# Teensy41Memory.net
KiCad netlist of a schematic drawn in EAGLE
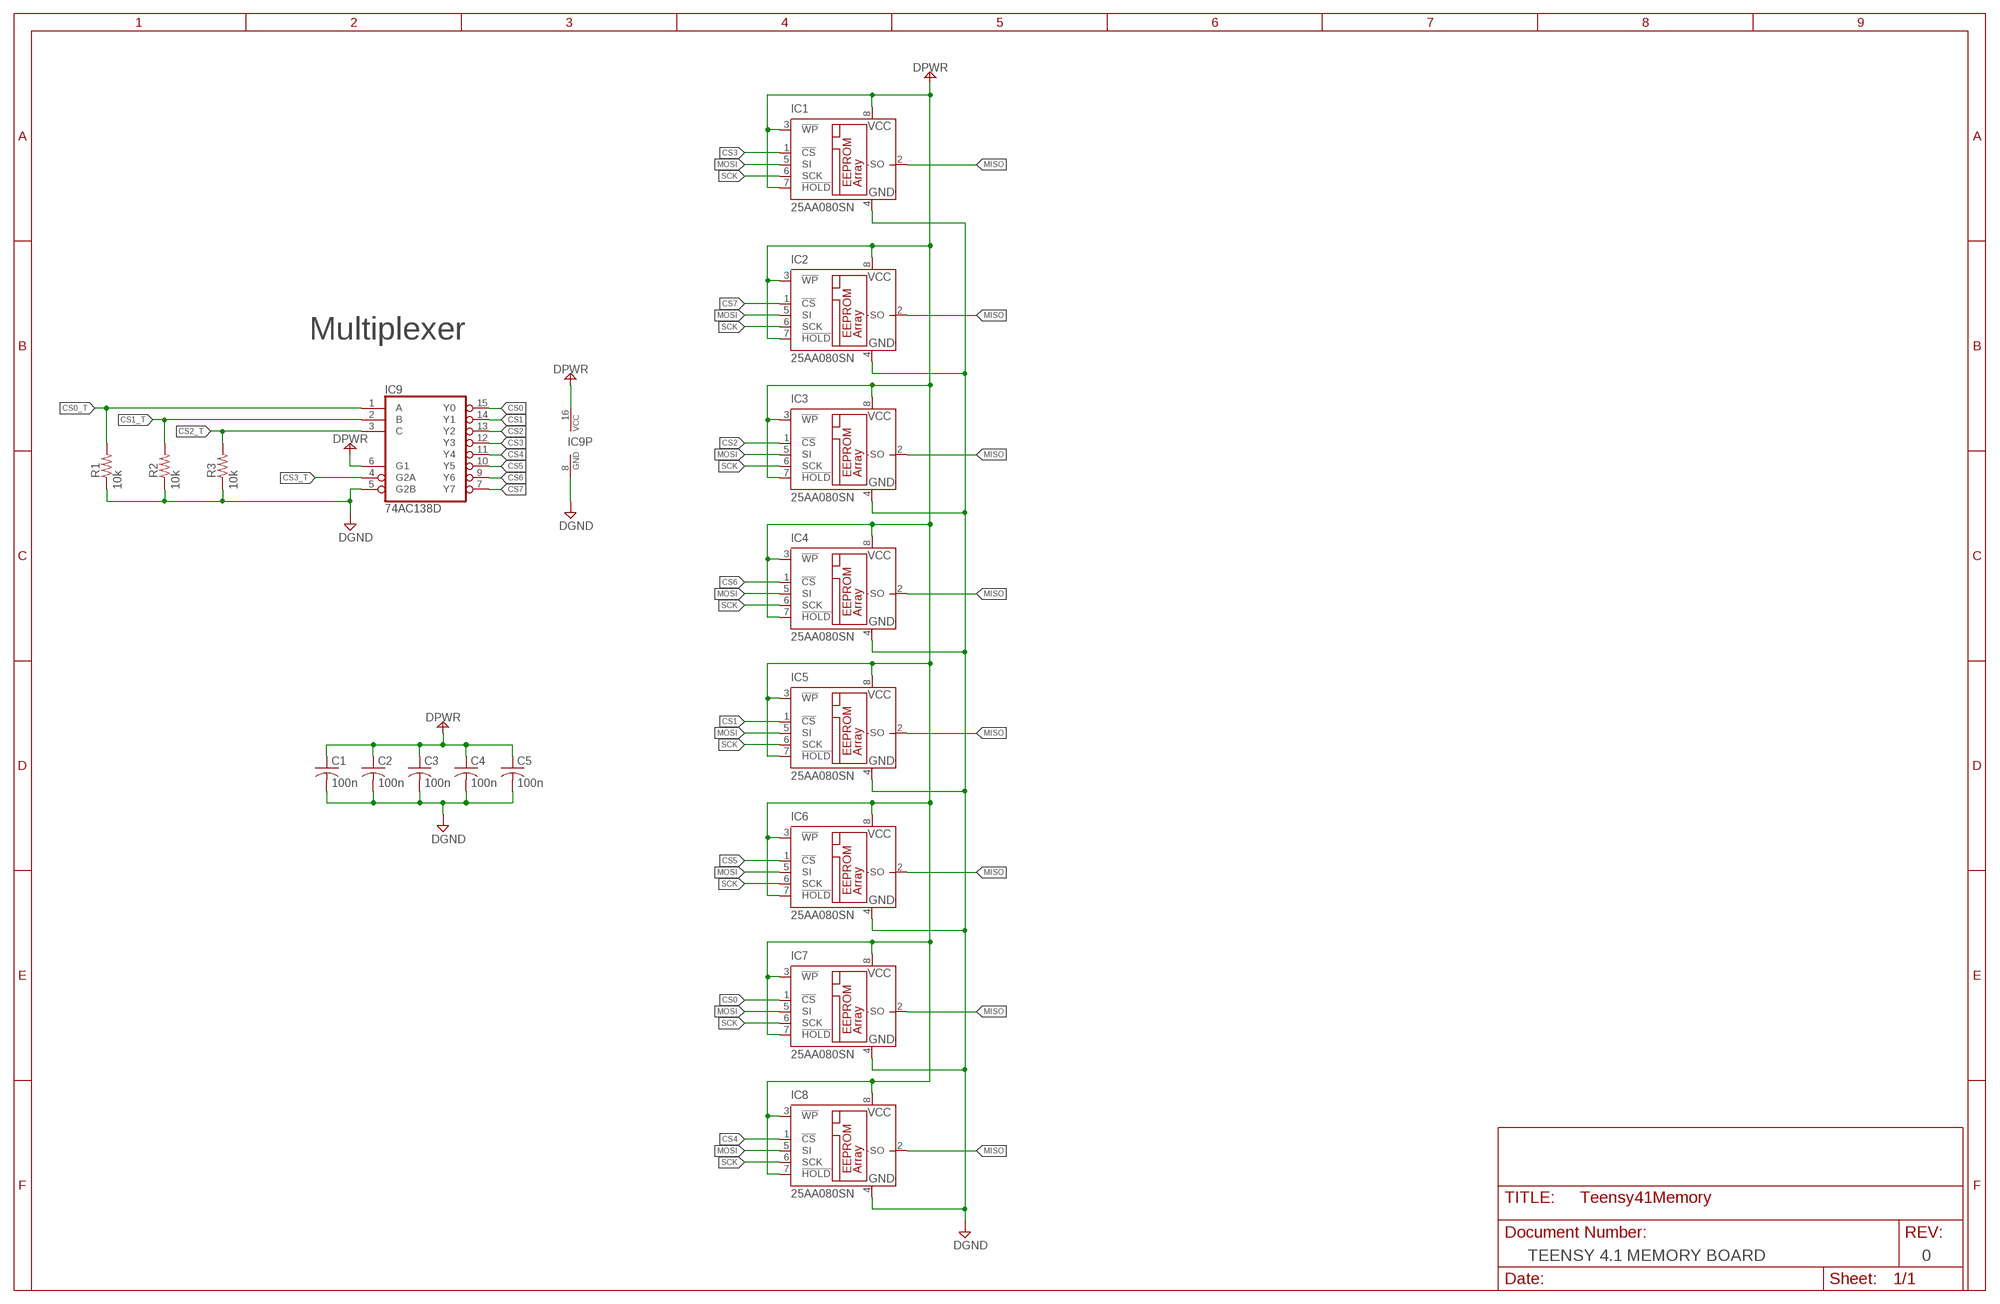
[diagram p0: schematic, sheet 1]

(export (version "E")
  (design (tool "Eeschema 10.0.6"))
  (components
    (comp (ref "C1")
      (value "100n")
      (footprint "eagle-import:C0603")
      (libsource (lib "eagle-import") (part "CB"))
    )
    (comp (ref "C2")
      (value "100n")
      (footprint "eagle-import:C0603")
      (libsource (lib "eagle-import") (part "CB"))
    )
    (comp (ref "C3")
      (value "100n")
      (footprint "eagle-import:C0603")
      (libsource (lib "eagle-import") (part "CB"))
    )
    (comp (ref "C4")
      (value "100n")
      (footprint "eagle-import:C0603")
      (libsource (lib "eagle-import") (part "CB"))
    )
    (comp (ref "C5")
      (value "100n")
      (footprint "eagle-import:C0603")
      (libsource (lib "eagle-import") (part "CB"))
    )
    (comp (ref "IC1")
      (value "25AA080SN")
      (footprint "eagle-import:SO-08")
      (fields (field (name "MF") "MICROCHIP") (field (name "MPN") "25AA080/SN"))
      (libsource (lib "eagle-import") (part "25SNAA080"))
    )
    (comp (ref "IC2")
      (value "25AA080SN")
      (footprint "eagle-import:SO-08")
      (fields (field (name "MF") "MICROCHIP") (field (name "MPN") "25AA080/SN"))
      (libsource (lib "eagle-import") (part "25SNAA080"))
    )
    (comp (ref "IC3")
      (value "25AA080SN")
      (footprint "eagle-import:SO-08")
      (fields (field (name "MF") "MICROCHIP") (field (name "MPN") "25AA080/SN"))
      (libsource (lib "eagle-import") (part "25SNAA080"))
    )
    (comp (ref "IC4")
      (value "25AA080SN")
      (footprint "eagle-import:SO-08")
      (fields (field (name "MF") "MICROCHIP") (field (name "MPN") "25AA080/SN"))
      (libsource (lib "eagle-import") (part "25SNAA080"))
    )
    (comp (ref "IC5")
      (value "25AA080SN")
      (footprint "eagle-import:SO-08")
      (fields (field (name "MF") "MICROCHIP") (field (name "MPN") "25AA080/SN"))
      (libsource (lib "eagle-import") (part "25SNAA080"))
    )
    (comp (ref "IC6")
      (value "25AA080SN")
      (footprint "eagle-import:SO-08")
      (fields (field (name "MF") "MICROCHIP") (field (name "MPN") "25AA080/SN"))
      (libsource (lib "eagle-import") (part "25SNAA080"))
    )
    (comp (ref "IC7")
      (value "25AA080SN")
      (footprint "eagle-import:SO-08")
      (fields (field (name "MF") "MICROCHIP") (field (name "MPN") "25AA080/SN"))
      (libsource (lib "eagle-import") (part "25SNAA080"))
    )
    (comp (ref "IC8")
      (value "25AA080SN")
      (footprint "eagle-import:SO-08")
      (fields (field (name "MF") "MICROCHIP") (field (name "MPN") "25AA080/SN"))
      (libsource (lib "eagle-import") (part "25SNAA080"))
    )
    (comp (ref "IC9")
      (value "74AC138D")
      (footprint "eagle-import:SO16")
      (libsource (lib "eagle-import") (part "74138DAC"))
    )
    (comp (ref "R1")
      (value "10k")
      (footprint "eagle-import:R0603")
      (libsource (lib "eagle-import") (part "RB"))
    )
    (comp (ref "R2")
      (value "10k")
      (footprint "eagle-import:R0603")
      (libsource (lib "eagle-import") (part "RB"))
    )
    (comp (ref "R3")
      (value "10k")
      (footprint "eagle-import:R0603")
      (libsource (lib "eagle-import") (part "RB"))
    )
  )
  (nets
    (net (code "1") (name "CS0") (class "Default")
      (node (ref "IC7") (pin "1") (pinfunction "~{CS}_1") (pintype "input"))
      (node (ref "IC9") (pin "15") (pinfunction "Y0_15") (pintype "output"))
    )
    (net (code "2") (name "CS0_T") (class "Default")
      (node (ref "IC9") (pin "1") (pinfunction "A_1") (pintype "input"))
      (node (ref "R1") (pin "2") (pinfunction "2_2") (pintype "passive"))
    )
    (net (code "3") (name "CS1") (class "Default")
      (node (ref "IC5") (pin "1") (pinfunction "~{CS}_1") (pintype "input"))
      (node (ref "IC9") (pin "14") (pinfunction "Y1_14") (pintype "output"))
    )
    (net (code "4") (name "CS1_T") (class "Default")
      (node (ref "IC9") (pin "2") (pinfunction "B_2") (pintype "input"))
      (node (ref "R2") (pin "2") (pinfunction "2_2") (pintype "passive"))
    )
    (net (code "5") (name "CS2") (class "Default")
      (node (ref "IC3") (pin "1") (pinfunction "~{CS}_1") (pintype "input"))
      (node (ref "IC9") (pin "13") (pinfunction "Y2_13") (pintype "output"))
    )
    (net (code "6") (name "CS2_T") (class "Default")
      (node (ref "IC9") (pin "3") (pinfunction "C_3") (pintype "input"))
      (node (ref "R3") (pin "2") (pinfunction "2_2") (pintype "passive"))
    )
    (net (code "7") (name "CS3") (class "Default")
      (node (ref "IC1") (pin "1") (pinfunction "~{CS}_1") (pintype "input"))
      (node (ref "IC9") (pin "12") (pinfunction "Y3_12") (pintype "output"))
    )
    (net (code "8") (name "CS3_T") (class "Default")
      (node (ref "IC9") (pin "4") (pinfunction "G2A_4") (pintype "input"))
    )
    (net (code "9") (name "CS4") (class "Default")
      (node (ref "IC8") (pin "1") (pinfunction "~{CS}_1") (pintype "input"))
      (node (ref "IC9") (pin "11") (pinfunction "Y4_11") (pintype "output"))
    )
    (net (code "10") (name "CS5") (class "Default")
      (node (ref "IC6") (pin "1") (pinfunction "~{CS}_1") (pintype "input"))
      (node (ref "IC9") (pin "10") (pinfunction "Y5_10") (pintype "output"))
    )
    (net (code "11") (name "CS6") (class "Default")
      (node (ref "IC4") (pin "1") (pinfunction "~{CS}_1") (pintype "input"))
      (node (ref "IC9") (pin "9") (pinfunction "Y6_9") (pintype "output"))
    )
    (net (code "12") (name "CS7") (class "Default")
      (node (ref "IC2") (pin "1") (pinfunction "~{CS}_1") (pintype "input"))
      (node (ref "IC9") (pin "7") (pinfunction "Y7_7") (pintype "output"))
    )
    (net (code "13") (name "DGND") (class "Default")
      (node (ref "C1") (pin "2") (pinfunction "2_2") (pintype "passive"))
      (node (ref "C2") (pin "2") (pinfunction "2_2") (pintype "passive"))
      (node (ref "C3") (pin "2") (pinfunction "2_2") (pintype "passive"))
      (node (ref "C4") (pin "2") (pinfunction "2_2") (pintype "passive"))
      (node (ref "C5") (pin "2") (pinfunction "2_2") (pintype "passive"))
      (node (ref "IC1") (pin "4") (pinfunction "GND_4") (pintype "power_in"))
      (node (ref "IC2") (pin "4") (pinfunction "GND_4") (pintype "power_in"))
      (node (ref "IC3") (pin "4") (pinfunction "GND_4") (pintype "power_in"))
      (node (ref "IC4") (pin "4") (pinfunction "GND_4") (pintype "power_in"))
      (node (ref "IC5") (pin "4") (pinfunction "GND_4") (pintype "power_in"))
      (node (ref "IC6") (pin "4") (pinfunction "GND_4") (pintype "power_in"))
      (node (ref "IC7") (pin "4") (pinfunction "GND_4") (pintype "power_in"))
      (node (ref "IC8") (pin "4") (pinfunction "GND_4") (pintype "power_in"))
      (node (ref "IC9") (pin "5") (pinfunction "G2B_5") (pintype "input"))
      (node (ref "IC9") (pin "8") (pinfunction "GND_8") (pintype "power_in"))
      (node (ref "R1") (pin "1") (pinfunction "1_1") (pintype "passive"))
      (node (ref "R2") (pin "1") (pinfunction "1_1") (pintype "passive"))
      (node (ref "R3") (pin "1") (pinfunction "1_1") (pintype "passive"))
    )
    (net (code "14") (name "DPWR") (class "Default")
      (node (ref "C1") (pin "1") (pinfunction "1_1") (pintype "passive"))
      (node (ref "C2") (pin "1") (pinfunction "1_1") (pintype "passive"))
      (node (ref "C3") (pin "1") (pinfunction "1_1") (pintype "passive"))
      (node (ref "C4") (pin "1") (pinfunction "1_1") (pintype "passive"))
      (node (ref "C5") (pin "1") (pinfunction "1_1") (pintype "passive"))
      (node (ref "IC1") (pin "3") (pinfunction "~{WP}_3") (pintype "input"))
      (node (ref "IC1") (pin "7") (pinfunction "~{HOLD}_7") (pintype "input"))
      (node (ref "IC1") (pin "8") (pinfunction "VCC_8") (pintype "power_in"))
      (node (ref "IC2") (pin "3") (pinfunction "~{WP}_3") (pintype "input"))
      (node (ref "IC2") (pin "7") (pinfunction "~{HOLD}_7") (pintype "input"))
      (node (ref "IC2") (pin "8") (pinfunction "VCC_8") (pintype "power_in"))
      (node (ref "IC3") (pin "3") (pinfunction "~{WP}_3") (pintype "input"))
      (node (ref "IC3") (pin "7") (pinfunction "~{HOLD}_7") (pintype "input"))
      (node (ref "IC3") (pin "8") (pinfunction "VCC_8") (pintype "power_in"))
      (node (ref "IC4") (pin "3") (pinfunction "~{WP}_3") (pintype "input"))
      (node (ref "IC4") (pin "7") (pinfunction "~{HOLD}_7") (pintype "input"))
      (node (ref "IC4") (pin "8") (pinfunction "VCC_8") (pintype "power_in"))
      (node (ref "IC5") (pin "3") (pinfunction "~{WP}_3") (pintype "input"))
      (node (ref "IC5") (pin "7") (pinfunction "~{HOLD}_7") (pintype "input"))
      (node (ref "IC5") (pin "8") (pinfunction "VCC_8") (pintype "power_in"))
      (node (ref "IC6") (pin "3") (pinfunction "~{WP}_3") (pintype "input"))
      (node (ref "IC6") (pin "7") (pinfunction "~{HOLD}_7") (pintype "input"))
      (node (ref "IC6") (pin "8") (pinfunction "VCC_8") (pintype "power_in"))
      (node (ref "IC7") (pin "3") (pinfunction "~{WP}_3") (pintype "input"))
      (node (ref "IC7") (pin "7") (pinfunction "~{HOLD}_7") (pintype "input"))
      (node (ref "IC7") (pin "8") (pinfunction "VCC_8") (pintype "power_in"))
      (node (ref "IC8") (pin "3") (pinfunction "~{WP}_3") (pintype "input"))
      (node (ref "IC8") (pin "7") (pinfunction "~{HOLD}_7") (pintype "input"))
      (node (ref "IC8") (pin "8") (pinfunction "VCC_8") (pintype "power_in"))
      (node (ref "IC9") (pin "16") (pinfunction "VCC_16") (pintype "power_in"))
      (node (ref "IC9") (pin "6") (pinfunction "G1_6") (pintype "input"))
    )
    (net (code "15") (name "MISO") (class "Default")
      (node (ref "IC1") (pin "2") (pinfunction "SO_2") (pintype "bidirectional"))
      (node (ref "IC2") (pin "2") (pinfunction "SO_2") (pintype "bidirectional"))
      (node (ref "IC3") (pin "2") (pinfunction "SO_2") (pintype "bidirectional"))
      (node (ref "IC4") (pin "2") (pinfunction "SO_2") (pintype "bidirectional"))
      (node (ref "IC5") (pin "2") (pinfunction "SO_2") (pintype "bidirectional"))
      (node (ref "IC6") (pin "2") (pinfunction "SO_2") (pintype "bidirectional"))
      (node (ref "IC7") (pin "2") (pinfunction "SO_2") (pintype "bidirectional"))
      (node (ref "IC8") (pin "2") (pinfunction "SO_2") (pintype "bidirectional"))
    )
    (net (code "16") (name "MOSI") (class "Default")
      (node (ref "IC1") (pin "5") (pinfunction "SI_5") (pintype "input"))
      (node (ref "IC2") (pin "5") (pinfunction "SI_5") (pintype "input"))
      (node (ref "IC3") (pin "5") (pinfunction "SI_5") (pintype "input"))
      (node (ref "IC4") (pin "5") (pinfunction "SI_5") (pintype "input"))
      (node (ref "IC5") (pin "5") (pinfunction "SI_5") (pintype "input"))
      (node (ref "IC6") (pin "5") (pinfunction "SI_5") (pintype "input"))
      (node (ref "IC7") (pin "5") (pinfunction "SI_5") (pintype "input"))
      (node (ref "IC8") (pin "5") (pinfunction "SI_5") (pintype "input"))
    )
    (net (code "17") (name "SCK") (class "Default")
      (node (ref "IC1") (pin "6") (pinfunction "SCK_6") (pintype "input"))
      (node (ref "IC2") (pin "6") (pinfunction "SCK_6") (pintype "input"))
      (node (ref "IC3") (pin "6") (pinfunction "SCK_6") (pintype "input"))
      (node (ref "IC4") (pin "6") (pinfunction "SCK_6") (pintype "input"))
      (node (ref "IC5") (pin "6") (pinfunction "SCK_6") (pintype "input"))
      (node (ref "IC6") (pin "6") (pinfunction "SCK_6") (pintype "input"))
      (node (ref "IC7") (pin "6") (pinfunction "SCK_6") (pintype "input"))
      (node (ref "IC8") (pin "6") (pinfunction "SCK_6") (pintype "input"))
    )
  )
)
